# TopPanel.net
KiCad netlist of a schematic drawn in EAGLE
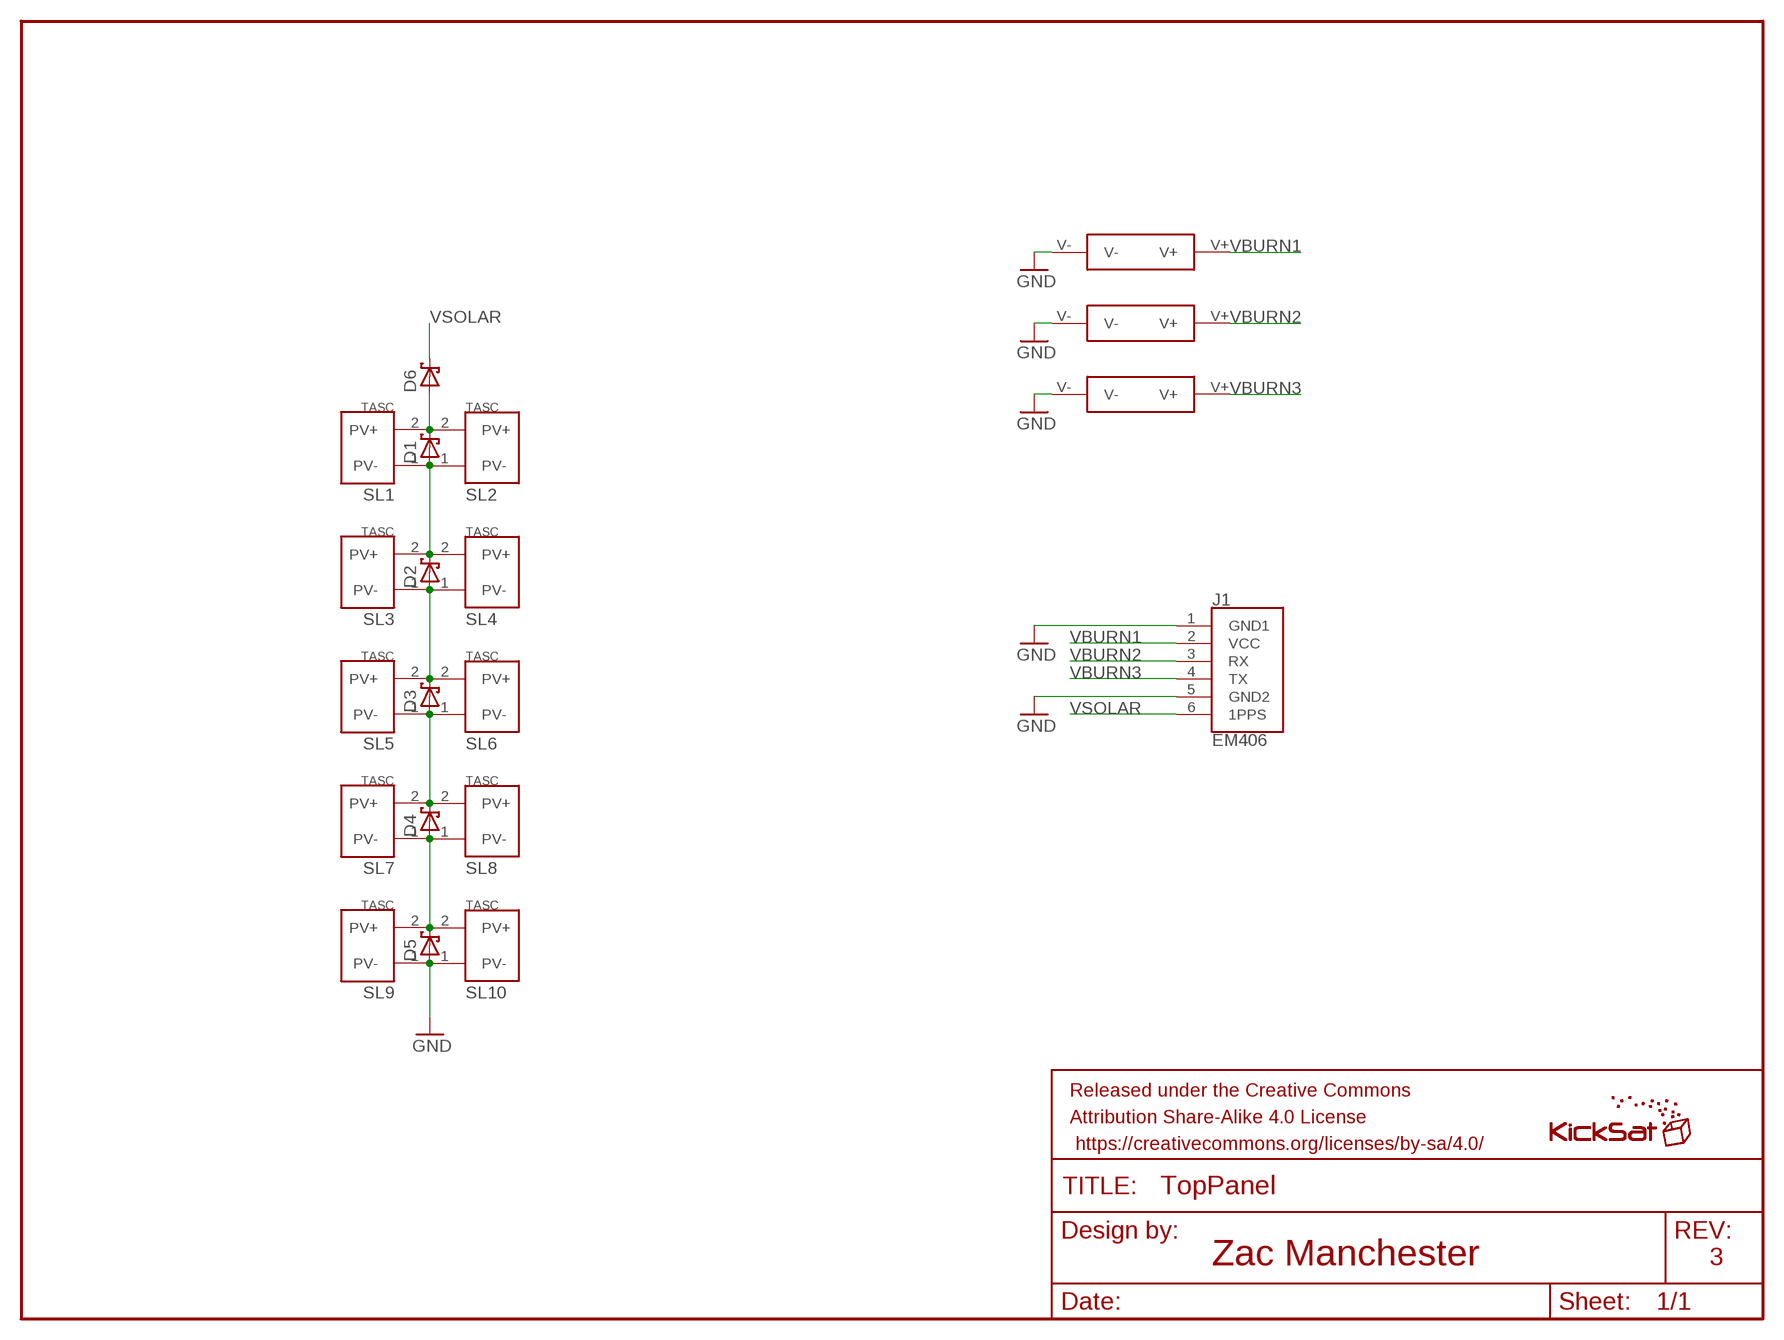
[diagram p0: schematic, sheet 1]

(export (version "E")
  (design (tool "Eeschema 10.0.6"))
  (components
    (comp (ref "D1")
      (value "SB_DIODE")
      (footprint "eagle-import:SB_DIODE")
      (libsource (lib "eagle-import") (part "SB_DIODE"))
    )
    (comp (ref "D2")
      (value "SB_DIODE")
      (footprint "eagle-import:SB_DIODE")
      (libsource (lib "eagle-import") (part "SB_DIODE"))
    )
    (comp (ref "D3")
      (value "SB_DIODE")
      (footprint "eagle-import:SB_DIODE")
      (libsource (lib "eagle-import") (part "SB_DIODE"))
    )
    (comp (ref "D4")
      (value "SB_DIODE")
      (footprint "eagle-import:SB_DIODE")
      (libsource (lib "eagle-import") (part "SB_DIODE"))
    )
    (comp (ref "D5")
      (value "SB_DIODE")
      (footprint "eagle-import:SB_DIODE")
      (libsource (lib "eagle-import") (part "SB_DIODE"))
    )
    (comp (ref "D6")
      (value "SB_DIODE")
      (footprint "eagle-import:SB_DIODE")
      (libsource (lib "eagle-import") (part "SB_DIODE"))
    )
    (comp (ref "FRAME1")
      (value "FRAME-LETTER")
      (footprint "eagle-import:CREATIVE_COMMONS")
      (libsource (lib "eagle-import") (part "FRAME-LETTER"))
    )
    (comp (ref "J1")
      (value "EM406")
      (footprint "eagle-import:1X06-1MM")
      (libsource (lib "eagle-import") (part "EM406"))
    )
    (comp (ref "SL1")
      (value "SOLAR_CELL")
      (footprint "eagle-import:SOLAR_CELL")
      (libsource (lib "eagle-import") (part "SOLAR_CELL"))
    )
    (comp (ref "SL2")
      (value "SOLAR_CELL")
      (footprint "eagle-import:SOLAR_CELL")
      (libsource (lib "eagle-import") (part "SOLAR_CELL"))
    )
    (comp (ref "SL3")
      (value "SOLAR_CELL")
      (footprint "eagle-import:SOLAR_CELL")
      (libsource (lib "eagle-import") (part "SOLAR_CELL"))
    )
    (comp (ref "SL4")
      (value "SOLAR_CELL")
      (footprint "eagle-import:SOLAR_CELL")
      (libsource (lib "eagle-import") (part "SOLAR_CELL"))
    )
    (comp (ref "SL5")
      (value "SOLAR_CELL")
      (footprint "eagle-import:SOLAR_CELL")
      (libsource (lib "eagle-import") (part "SOLAR_CELL"))
    )
    (comp (ref "SL6")
      (value "SOLAR_CELL")
      (footprint "eagle-import:SOLAR_CELL")
      (libsource (lib "eagle-import") (part "SOLAR_CELL"))
    )
    (comp (ref "SL7")
      (value "SOLAR_CELL")
      (footprint "eagle-import:SOLAR_CELL")
      (libsource (lib "eagle-import") (part "SOLAR_CELL"))
    )
    (comp (ref "SL8")
      (value "SOLAR_CELL")
      (footprint "eagle-import:SOLAR_CELL")
      (libsource (lib "eagle-import") (part "SOLAR_CELL"))
    )
    (comp (ref "SL9")
      (value "SOLAR_CELL")
      (footprint "eagle-import:SOLAR_CELL")
      (libsource (lib "eagle-import") (part "SOLAR_CELL"))
    )
    (comp (ref "SL10")
      (value "SOLAR_CELL")
      (footprint "eagle-import:SOLAR_CELL")
      (libsource (lib "eagle-import") (part "SOLAR_CELL"))
    )
    (comp (ref "U$1")
      (value "KICKSAT_LOGO")
      (footprint "eagle-import:KICKSAT_LOGO")
      (libsource (lib "eagle-import") (part "KICKSAT_LOGO"))
    )
    (comp (ref "U$2")
      (value "BURNWIRE")
      (footprint "eagle-import:BURNWIRE")
      (libsource (lib "eagle-import") (part "BURNWIRE"))
    )
    (comp (ref "U$3")
      (value "BURNWIRE")
      (footprint "eagle-import:BURNWIRE")
      (libsource (lib "eagle-import") (part "BURNWIRE"))
    )
    (comp (ref "U$4")
      (value "BURNWIRE")
      (footprint "eagle-import:BURNWIRE")
      (libsource (lib "eagle-import") (part "BURNWIRE"))
    )
  )
  (nets
    (net (code "1") (name "/VBURN1") (class "Default")
      (node (ref "J1") (pin "2") (pinfunction "VCC_2") (pintype "bidirectional"))
      (node (ref "U$2") (pin "V+") (pinfunction "V+_V+") (pintype "bidirectional"))
    )
    (net (code "2") (name "/VBURN2") (class "Default")
      (node (ref "J1") (pin "3") (pinfunction "RX_3") (pintype "bidirectional"))
      (node (ref "U$3") (pin "V+") (pinfunction "V+_V+") (pintype "bidirectional"))
    )
    (net (code "3") (name "/VBURN3") (class "Default")
      (node (ref "J1") (pin "4") (pinfunction "TX_4") (pintype "bidirectional"))
      (node (ref "U$4") (pin "V+") (pinfunction "V+_V+") (pintype "bidirectional"))
    )
    (net (code "4") (name "/VSOLAR") (class "Default")
      (node (ref "D6") (pin "NEG") (pinfunction "NEG_NEG") (pintype "passive"))
      (node (ref "J1") (pin "6") (pinfunction "1PPS_6") (pintype "bidirectional"))
    )
    (net (code "5") (name "GND") (class "Default")
      (node (ref "D5") (pin "POS") (pinfunction "POS_POS") (pintype "passive"))
      (node (ref "J1") (pin "1") (pinfunction "GND1_1") (pintype "bidirectional"))
      (node (ref "J1") (pin "5") (pinfunction "GND2_5") (pintype "bidirectional"))
      (node (ref "SL10") (pin "1") (pinfunction "PV-_1") (pintype "bidirectional"))
      (node (ref "SL9") (pin "1") (pinfunction "PV-_1") (pintype "bidirectional"))
      (node (ref "U$2") (pin "V-") (pinfunction "V-_V-") (pintype "bidirectional"))
      (node (ref "U$3") (pin "V-") (pinfunction "V-_V-") (pintype "bidirectional"))
      (node (ref "U$4") (pin "V-") (pinfunction "V-_V-") (pintype "bidirectional"))
    )
    (net (code "6") (name "Net-(SL1-PV+)") (class "Default")
      (node (ref "D1") (pin "NEG") (pinfunction "NEG_NEG") (pintype "passive"))
      (node (ref "D6") (pin "POS") (pinfunction "POS_POS") (pintype "passive"))
      (node (ref "SL1") (pin "2") (pinfunction "PV+_2") (pintype "bidirectional"))
      (node (ref "SL2") (pin "2") (pinfunction "PV+_2") (pintype "bidirectional"))
    )
    (net (code "7") (name "Net-(SL1-PV-)") (class "Default")
      (node (ref "D1") (pin "POS") (pinfunction "POS_POS") (pintype "passive"))
      (node (ref "D2") (pin "NEG") (pinfunction "NEG_NEG") (pintype "passive"))
      (node (ref "SL1") (pin "1") (pinfunction "PV-_1") (pintype "bidirectional"))
      (node (ref "SL2") (pin "1") (pinfunction "PV-_1") (pintype "bidirectional"))
      (node (ref "SL3") (pin "2") (pinfunction "PV+_2") (pintype "bidirectional"))
      (node (ref "SL4") (pin "2") (pinfunction "PV+_2") (pintype "bidirectional"))
    )
    (net (code "8") (name "Net-(SL3-PV-)") (class "Default")
      (node (ref "D2") (pin "POS") (pinfunction "POS_POS") (pintype "passive"))
      (node (ref "D3") (pin "NEG") (pinfunction "NEG_NEG") (pintype "passive"))
      (node (ref "SL3") (pin "1") (pinfunction "PV-_1") (pintype "bidirectional"))
      (node (ref "SL4") (pin "1") (pinfunction "PV-_1") (pintype "bidirectional"))
      (node (ref "SL5") (pin "2") (pinfunction "PV+_2") (pintype "bidirectional"))
      (node (ref "SL6") (pin "2") (pinfunction "PV+_2") (pintype "bidirectional"))
    )
    (net (code "9") (name "Net-(SL5-PV-)") (class "Default")
      (node (ref "D3") (pin "POS") (pinfunction "POS_POS") (pintype "passive"))
      (node (ref "D4") (pin "NEG") (pinfunction "NEG_NEG") (pintype "passive"))
      (node (ref "SL5") (pin "1") (pinfunction "PV-_1") (pintype "bidirectional"))
      (node (ref "SL6") (pin "1") (pinfunction "PV-_1") (pintype "bidirectional"))
      (node (ref "SL7") (pin "2") (pinfunction "PV+_2") (pintype "bidirectional"))
      (node (ref "SL8") (pin "2") (pinfunction "PV+_2") (pintype "bidirectional"))
    )
    (net (code "10") (name "Net-(SL10-PV+)") (class "Default")
      (node (ref "D4") (pin "POS") (pinfunction "POS_POS") (pintype "passive"))
      (node (ref "D5") (pin "NEG") (pinfunction "NEG_NEG") (pintype "passive"))
      (node (ref "SL10") (pin "2") (pinfunction "PV+_2") (pintype "bidirectional"))
      (node (ref "SL7") (pin "1") (pinfunction "PV-_1") (pintype "bidirectional"))
      (node (ref "SL8") (pin "1") (pinfunction "PV-_1") (pintype "bidirectional"))
      (node (ref "SL9") (pin "2") (pinfunction "PV+_2") (pintype "bidirectional"))
    )
  )
)
